# SleepTrackerPoC.net
KiCad netlist of a schematic drawn in Altium Designer
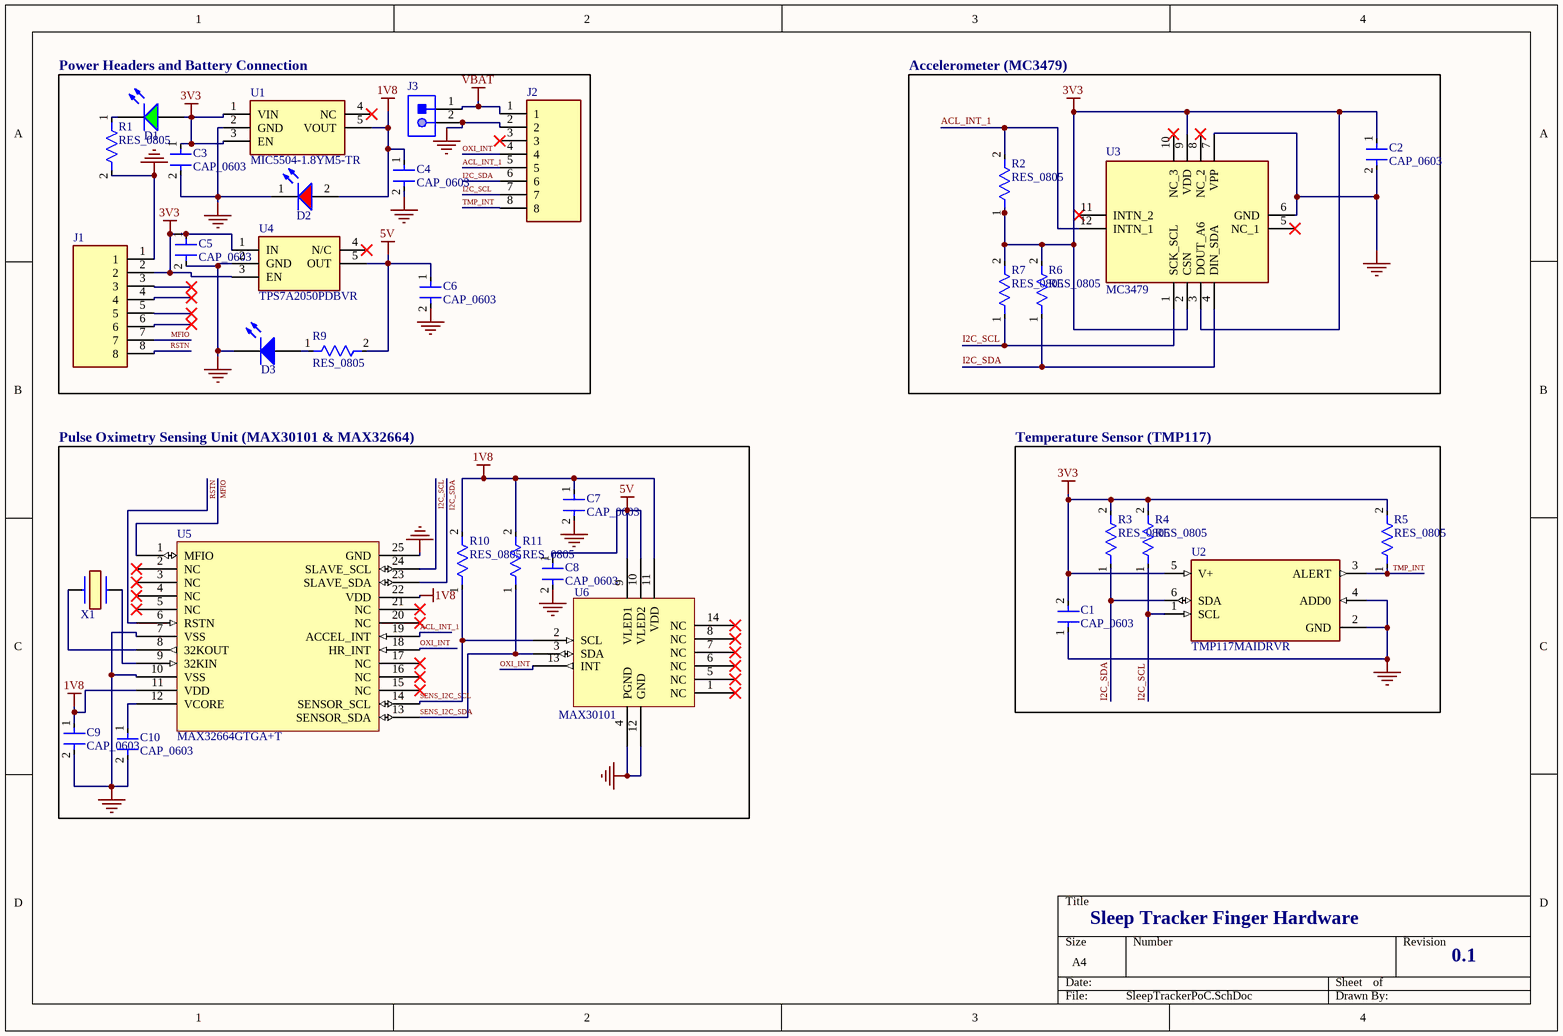
[diagram p0: SleepTrackerPoC.SchDoc]

(export (version "E")
  (design (tool "Eeschema 10.0.6"))
  (components
    (comp (ref "C1")
      (value "CAP_0603")
      (footprint "CAP_0603")
      (libsource (lib "SleepTrackerPoCSchLib") (part "Capacitor SMT 0603"))
    )
    (comp (ref "C2")
      (value "CAP_0603")
      (footprint "CAP_0603")
      (libsource (lib "SleepTrackerPoCSchLib") (part "Capacitor SMT 0603"))
    )
    (comp (ref "C3")
      (value "CAP_0603")
      (footprint "CAP_0603")
      (libsource (lib "SleepTrackerPoCSchLib") (part "Capacitor SMT 0603"))
    )
    (comp (ref "C4")
      (value "CAP_0603")
      (footprint "CAP_0603")
      (libsource (lib "SleepTrackerPoCSchLib") (part "Capacitor SMT 0603"))
    )
    (comp (ref "C5")
      (value "CAP_0603")
      (footprint "CAP_0603")
      (libsource (lib "SleepTrackerPoCSchLib") (part "Capacitor SMT 0603"))
    )
    (comp (ref "C6")
      (value "CAP_0603")
      (footprint "CAP_0603")
      (libsource (lib "SleepTrackerPoCSchLib") (part "Capacitor SMT 0603"))
    )
    (comp (ref "C7")
      (value "CAP_0603")
      (footprint "CAP_0603")
      (libsource (lib "SleepTrackerPoCSchLib") (part "Capacitor SMT 0603"))
    )
    (comp (ref "C8")
      (value "CAP_0603")
      (footprint "CAP_0603")
      (libsource (lib "SleepTrackerPoCSchLib") (part "Capacitor SMT 0603"))
    )
    (comp (ref "C9")
      (value "CAP_0603")
      (footprint "CAP_0603")
      (libsource (lib "SleepTrackerPoCSchLib") (part "Capacitor SMT 0603"))
    )
    (comp (ref "C10")
      (value "CAP_0603")
      (footprint "CAP_0603")
      (libsource (lib "SleepTrackerPoCSchLib") (part "Capacitor SMT 0603"))
    )
    (comp (ref "D1")
      (value "150080VS75000")
      (footprint "WL-SMCW_0805_150080xx75000")
      (description "WL-SMCW SMT Mono-Color Chip LED Waterclear")
      (libsource (lib "Altium Content Vault") (part "LED_Green_2A-1K"))
    )
    (comp (ref "D2")
      (value "150080RS75000")
      (footprint "WL-SMCW_0805_150080xx75000")
      (description "LED Uni-Color Red 630nm 2-Pin Chip 0805(2012Metric) T/R")
      (libsource (lib "Altium Content Vault") (part "LED_Red_2A-1K"))
    )
    (comp (ref "D3")
      (value "150080BS75000")
      (footprint "WL-SMCW_0805_150080xx75000")
      (description "Led, Blue, 470 Nm, 3.2 V, 30 Ma, 145 Mcd Rohs Compliant: Yes")
      (libsource (lib "Altium Content Vault") (part "LED_Blue_2A-1K"))
    )
    (comp (ref "J1")
      (value "90147-1108")
      (footprint "RHDR8W70P0X254_1X8_2017X244X870P")
      (description "Headers & Wire Housings 8CKT VERT SR CON")
      (fields (field (name "MOUSER PART NUMBER") "538-90147-1108"))
      (libsource (lib "SleepTrackerPoCSchLib") (part "90147-1108"))
    )
    (comp (ref "J2")
      (value "90147-1108")
      (footprint "RHDR8W70P0X254_1X8_2017X244X870P")
      (description "Headers & Wire Housings 8CKT VERT SR CON")
      (fields (field (name "MOUSER PART NUMBER") "538-90147-1108"))
      (libsource (lib "") (part "90147-1108_1"))
    )
    (comp (ref "J3")
      (value "S2B-PH-K-S(LF)(SN)")
      (footprint "JST-S2B-PH-K-S_V")
      (fields (field (name "TOLERANCE") "20%"))
      (libsource (lib "Altium Content Vault") (part "CN-1P-M-R2"))
    )
    (comp (ref "R1")
      (value "RES_0805")
      (footprint "RES_0805")
      (libsource (lib "SleepTrackerPoCSchLib") (part "Resistor SMT 0805"))
    )
    (comp (ref "R2")
      (value "RES_0805")
      (footprint "RES_0805")
      (libsource (lib "SleepTrackerPoCSchLib") (part "Resistor SMT 0805"))
    )
    (comp (ref "R3")
      (value "RES_0805")
      (footprint "RES_0805")
      (libsource (lib "SleepTrackerPoCSchLib") (part "Resistor SMT 0805"))
    )
    (comp (ref "R4")
      (value "RES_0805")
      (footprint "RES_0805")
      (libsource (lib "SleepTrackerPoCSchLib") (part "Resistor SMT 0805"))
    )
    (comp (ref "R5")
      (value "RES_0805")
      (footprint "RES_0805")
      (libsource (lib "SleepTrackerPoCSchLib") (part "Resistor SMT 0805"))
    )
    (comp (ref "R6")
      (value "RES_0805")
      (footprint "RES_0805")
      (libsource (lib "SleepTrackerPoCSchLib") (part "Resistor SMT 0805"))
    )
    (comp (ref "R7")
      (value "RES_0805")
      (footprint "RES_0805")
      (libsource (lib "SleepTrackerPoCSchLib") (part "Resistor SMT 0805"))
    )
    (comp (ref "R9")
      (value "RES_0805")
      (footprint "RES_0805")
      (libsource (lib "SleepTrackerPoCSchLib") (part "Resistor SMT 0805"))
    )
    (comp (ref "R10")
      (value "RES_0805")
      (footprint "RES_0805")
      (libsource (lib "SleepTrackerPoCSchLib") (part "Resistor SMT 0805"))
    )
    (comp (ref "R11")
      (value "RES_0805")
      (footprint "RES_0805")
      (libsource (lib "SleepTrackerPoCSchLib") (part "Resistor SMT 0805"))
    )
    (comp (ref "U1")
      (value "MIC5504-1.8YM5-TR")
      (footprint "SOT95P280X145-5N")
      (description "Linear Voltage Regulator IC Positive Fixed Output 1.8V 300mA SOT-23-5")
      (fields (field (name "MOUSER PART NUMBER") "998-MIC5504-1.8YM5TR"))
      (libsource (lib "SleepTrackerPoCSchLib") (part "MIC5504-1.8YM5-TR"))
    )
    (comp (ref "U2")
      (value "TMP117MAIDRVR")
      (footprint "FP-DRV0006B-IPC_C")
      (description "TEMPERATURE SENSOR")
      (libsource (lib "Altium Content Vault") (part "6af1b5b9c3f1ef8afed83eb3745dfc1"))
    )
    (comp (ref "U3")
      (value "MC3479")
      (footprint "MC3479")
      (description "Accelerometers Small Digital 3-axis Accelerometer Sensor")
      (fields (field (name "MOUSER PART NUMBER") "498-MC3479"))
      (libsource (lib "SleepTrackerPoCSchLib") (part "MC3479"))
    )
    (comp (ref "U4")
      (value "TPS7A2050PDBVR")
      (footprint "SOT95P280X145-5N")
      (fields (field (name "MOUSER PART NUMBER") "595-TPS7A2050PDBVR"))
      (libsource (lib "SleepTrackerPoCSchLib") (part "TPS7A2050PDBVR"))
    )
    (comp (ref "U5")
      (value "MAX32664GTGA+T")
      (footprint "MAX32664")
      (description "Maxim Integrated MAX32664GTGA+T Sensor Hub")
      (libsource (lib "SleepTrackerPoCSchLib") (part "MAX32664GTGA+T"))
    )
    (comp (ref "U6")
      (value "MAX30101")
      (footprint "MAX30101")
      (description "Maxim Integrated MAX30101 Oximetry Sensor")
      (libsource (lib "SleepTrackerPoCSchLib") (part "MAX30101"))
    )
    (comp (ref "X1")
      (value "CFS-20632768DZBB")
      (footprint "CFS20632768DZBB")
      (description "32.768 kHz +/-20ppm Crystal 6pF 35 kOhms Cylindrical Can, Radial")
      (fields (field (name "MOUSER PART NUMBER") "695-CFS-20632768DZBB"))
      (libsource (lib "SleepTrackerPoCSchLib") (part "CFS-20632768DZBB"))
    )
  )
  (nets
    (net (code "1") (name "/ACL_INT_1") (class "Default")
      (node (ref "J2") (pin "5") (pinfunction "5_5") (pintype "passive"))
      (node (ref "R2") (pin "2") (pintype "passive"))
      (node (ref "U3") (pin "12") (pinfunction "INTN_1_12") (pintype "passive"))
      (node (ref "U5") (pin "19") (pinfunction "ACCEL_INT_19") (pintype "input"))
    )
    (net (code "2") (name "/I2C_SCL") (class "Default")
      (node (ref "J2") (pin "7") (pinfunction "7_7") (pintype "passive"))
      (node (ref "R4") (pin "1") (pintype "passive"))
      (node (ref "R7") (pin "1") (pintype "passive"))
      (node (ref "U2") (pin "1") (pinfunction "SCL_1") (pintype "input"))
      (node (ref "U3") (pin "1") (pinfunction "SCK_SCL_1") (pintype "passive"))
      (node (ref "U5") (pin "24") (pinfunction "SLAVE_SCL_24") (pintype "bidirectional"))
    )
    (net (code "3") (name "/I2C_SDA") (class "Default")
      (node (ref "J2") (pin "6") (pinfunction "6_6") (pintype "passive"))
      (node (ref "R3") (pin "1") (pintype "passive"))
      (node (ref "R6") (pin "1") (pintype "passive"))
      (node (ref "U2") (pin "6") (pinfunction "SDA_6") (pintype "bidirectional"))
      (node (ref "U3") (pin "4") (pinfunction "DIN_SDA_4") (pintype "passive"))
      (node (ref "U5") (pin "23") (pinfunction "SLAVE_SDA_23") (pintype "bidirectional"))
    )
    (net (code "4") (name "/MFIO") (class "Default")
      (node (ref "J1") (pin "7") (pinfunction "7_7") (pintype "passive"))
      (node (ref "U5") (pin "1") (pinfunction "MFIO_1") (pintype "bidirectional"))
    )
    (net (code "5") (name "/OXI_INT") (class "Default")
      (node (ref "J2") (pin "4") (pinfunction "4_4") (pintype "passive"))
      (node (ref "U5") (pin "18") (pinfunction "HR_INT_18") (pintype "input"))
      (node (ref "U6") (pin "13") (pinfunction "INT_13") (pintype "output"))
    )
    (net (code "6") (name "/RSTN") (class "Default")
      (node (ref "J1") (pin "8") (pinfunction "8_8") (pintype "passive"))
      (node (ref "U5") (pin "6") (pinfunction "RSTN_6") (pintype "input"))
    )
    (net (code "7") (name "/SENS_I2C_SCL") (class "Default")
      (node (ref "R10") (pin "1") (pintype "passive"))
      (node (ref "U5") (pin "14") (pinfunction "SENSOR_SCL_14") (pintype "bidirectional"))
      (node (ref "U6") (pin "2") (pinfunction "SCL_2") (pintype "input"))
    )
    (net (code "8") (name "/SENS_I2C_SDA") (class "Default")
      (node (ref "R11") (pin "1") (pintype "passive"))
      (node (ref "U5") (pin "13") (pinfunction "SENSOR_SDA_13") (pintype "bidirectional"))
      (node (ref "U6") (pin "3") (pinfunction "SDA_3") (pintype "bidirectional"))
    )
    (net (code "9") (name "/TMP_INT") (class "Default")
      (node (ref "J2") (pin "8") (pinfunction "8_8") (pintype "passive"))
      (node (ref "R5") (pin "1") (pintype "passive"))
      (node (ref "U2") (pin "3") (pinfunction "ALERT_3") (pintype "output"))
    )
    (net (code "10") (name "1V8") (class "Default")
      (node (ref "C4") (pin "1") (pintype "passive"))
      (node (ref "C7") (pin "1") (pintype "passive"))
      (node (ref "C9") (pin "1") (pintype "passive"))
      (node (ref "D2") (pin "2") (pinfunction "A_2") (pintype "passive"))
      (node (ref "R10") (pin "2") (pintype "passive"))
      (node (ref "R11") (pin "2") (pintype "passive"))
      (node (ref "U1") (pin "5") (pinfunction "VOUT_5") (pintype "passive"))
      (node (ref "U5") (pin "11") (pinfunction "VDD_11") (pintype "power_in"))
      (node (ref "U5") (pin "22") (pinfunction "VDD_22") (pintype "power_in"))
      (node (ref "U6") (pin "11") (pinfunction "VDD_11") (pintype "power_in"))
    )
    (net (code "11") (name "3V3") (class "Default")
      (node (ref "C1") (pin "2") (pintype "passive"))
      (node (ref "C2") (pin "1") (pintype "passive"))
      (node (ref "C3") (pin "1") (pintype "passive"))
      (node (ref "C5") (pin "1") (pintype "passive"))
      (node (ref "D1") (pin "2") (pinfunction "A_2") (pintype "passive"))
      (node (ref "J1") (pin "2") (pinfunction "2_2") (pintype "passive"))
      (node (ref "R2") (pin "1") (pintype "passive"))
      (node (ref "R3") (pin "2") (pintype "passive"))
      (node (ref "R4") (pin "2") (pintype "passive"))
      (node (ref "R5") (pin "2") (pintype "passive"))
      (node (ref "R6") (pin "2") (pintype "passive"))
      (node (ref "R7") (pin "2") (pintype "passive"))
      (node (ref "U1") (pin "1") (pinfunction "VIN_1") (pintype "passive"))
      (node (ref "U1") (pin "3") (pinfunction "EN_3") (pintype "passive"))
      (node (ref "U2") (pin "5") (pinfunction "V+_5") (pintype "input"))
      (node (ref "U3") (pin "2") (pinfunction "CSN_2") (pintype "passive"))
      (node (ref "U3") (pin "3") (pinfunction "DOUT_A6_3") (pintype "passive"))
      (node (ref "U3") (pin "9") (pinfunction "VDD_9") (pintype "passive"))
      (node (ref "U4") (pin "1") (pinfunction "IN_1") (pintype "passive"))
      (node (ref "U4") (pin "3") (pinfunction "EN_3") (pintype "passive"))
    )
    (net (code "12") (name "5V") (class "Default")
      (node (ref "C6") (pin "1") (pintype "passive"))
      (node (ref "C8") (pin "1") (pintype "passive"))
      (node (ref "R9") (pin "2") (pintype "passive"))
      (node (ref "U4") (pin "5") (pinfunction "OUT_5") (pintype "passive"))
      (node (ref "U6") (pin "10") (pinfunction "VLED2_10") (pintype "power_in"))
      (node (ref "U6") (pin "9") (pinfunction "VLED1_9") (pintype "power_in"))
    )
    (net (code "13") (name "GND") (class "Default")
      (node (ref "C1") (pin "1") (pintype "passive"))
      (node (ref "C10") (pin "2") (pintype "passive"))
      (node (ref "C2") (pin "2") (pintype "passive"))
      (node (ref "C3") (pin "2") (pintype "passive"))
      (node (ref "C4") (pin "2") (pintype "passive"))
      (node (ref "C5") (pin "2") (pintype "passive"))
      (node (ref "C6") (pin "2") (pintype "passive"))
      (node (ref "C7") (pin "2") (pintype "passive"))
      (node (ref "C8") (pin "2") (pintype "passive"))
      (node (ref "C9") (pin "2") (pintype "passive"))
      (node (ref "D2") (pin "1") (pinfunction "K_1") (pintype "passive"))
      (node (ref "D3") (pin "1") (pinfunction "K_1") (pintype "passive"))
      (node (ref "J1") (pin "1") (pinfunction "1_1") (pintype "passive"))
      (node (ref "J2") (pin "2") (pinfunction "2_2") (pintype "passive"))
      (node (ref "J3") (pin "2") (pinfunction "2_2") (pintype "passive"))
      (node (ref "R1") (pin "2") (pintype "passive"))
      (node (ref "U1") (pin "2") (pinfunction "GND_2") (pintype "passive"))
      (node (ref "U2") (pin "2") (pinfunction "GND_2") (pintype "power_in"))
      (node (ref "U2") (pin "4") (pinfunction "ADD0_4") (pintype "input"))
      (node (ref "U3") (pin "6") (pinfunction "GND_6") (pintype "passive"))
      (node (ref "U3") (pin "7") (pinfunction "VPP_7") (pintype "passive"))
      (node (ref "U4") (pin "2") (pinfunction "GND_2") (pintype "passive"))
      (node (ref "U5") (pin "10") (pinfunction "VSS_10") (pintype "power_in"))
      (node (ref "U5") (pin "25") (pinfunction "GND_25") (pintype "power_in"))
      (node (ref "U5") (pin "7") (pinfunction "VSS_7") (pintype "power_in"))
      (node (ref "U6") (pin "12") (pinfunction "GND_12") (pintype "power_in"))
      (node (ref "U6") (pin "4") (pinfunction "PGND_4") (pintype "power_in"))
    )
    (net (code "14") (name "Net-(D1-K)") (class "Default")
      (node (ref "D1") (pin "1") (pinfunction "K_1") (pintype "passive"))
      (node (ref "R1") (pin "1") (pintype "passive"))
    )
    (net (code "15") (name "Net-(D3-A)") (class "Default")
      (node (ref "D3") (pin "2") (pinfunction "A_2") (pintype "passive"))
      (node (ref "R9") (pin "1") (pintype "passive"))
    )
    (net (code "16") (name "Net-(U5-32KIN)") (class "Default")
      (node (ref "U5") (pin "9") (pinfunction "32KIN_9") (pintype "input"))
      (node (ref "X1") (pin "1") (pinfunction "1_1") (pintype "passive"))
    )
    (net (code "17") (name "Net-(U5-32KOUT)") (class "Default")
      (node (ref "U5") (pin "8") (pinfunction "32KOUT_8") (pintype "output"))
      (node (ref "X1") (pin "2") (pinfunction "2_2") (pintype "passive"))
    )
    (net (code "18") (name "Net-(U5-VCORE)") (class "Default")
      (node (ref "C10") (pin "1") (pintype "passive"))
      (node (ref "U5") (pin "12") (pinfunction "VCORE_12") (pintype "power_in"))
    )
    (net (code "19") (name "VBAT") (class "Default")
      (node (ref "J2") (pin "1") (pinfunction "1_1") (pintype "passive"))
      (node (ref "J3") (pin "1") (pinfunction "1_1") (pintype "passive"))
    )
    (net (code "20") (name "unconnected-(J1-Pad3)") (class "Default")
      (node (ref "J1") (pin "3") (pinfunction "3_3") (pintype "passive+no_connect"))
    )
    (net (code "21") (name "unconnected-(J1-Pad4)") (class "Default")
      (node (ref "J1") (pin "4") (pinfunction "4_4") (pintype "passive+no_connect"))
    )
    (net (code "22") (name "unconnected-(J1-Pad5)") (class "Default")
      (node (ref "J1") (pin "5") (pinfunction "5_5") (pintype "passive+no_connect"))
    )
    (net (code "23") (name "unconnected-(J1-Pad6)") (class "Default")
      (node (ref "J1") (pin "6") (pinfunction "6_6") (pintype "passive+no_connect"))
    )
    (net (code "24") (name "unconnected-(J2-Pad3)") (class "Default")
      (node (ref "J2") (pin "3") (pinfunction "3_3") (pintype "passive+no_connect"))
    )
    (net (code "25") (name "unconnected-(U1-NC-Pad4)") (class "Default")
      (node (ref "U1") (pin "4") (pinfunction "NC_4") (pintype "passive+no_connect"))
    )
    (net (code "26") (name "unconnected-(U3-INTN_2-Pad11)") (class "Default")
      (node (ref "U3") (pin "11") (pinfunction "INTN_2_11") (pintype "passive+no_connect"))
    )
    (net (code "27") (name "unconnected-(U3-NC_1-Pad5)") (class "Default")
      (node (ref "U3") (pin "5") (pinfunction "NC_1_5") (pintype "passive+no_connect"))
    )
    (net (code "28") (name "unconnected-(U3-NC_2-Pad8)") (class "Default")
      (node (ref "U3") (pin "8") (pinfunction "NC_2_8") (pintype "passive+no_connect"))
    )
    (net (code "29") (name "unconnected-(U3-NC_3-Pad10)") (class "Default")
      (node (ref "U3") (pin "10") (pinfunction "NC_3_10") (pintype "passive+no_connect"))
    )
    (net (code "30") (name "unconnected-(U4-N{slash}C-Pad4)") (class "Default")
      (node (ref "U4") (pin "4") (pinfunction "N/C_4") (pintype "passive+no_connect"))
    )
    (net (code "31") (name "unconnected-(U5-NC-Pad2)") (class "Default")
      (node (ref "U5") (pin "2") (pinfunction "NC_2") (pintype "passive+no_connect"))
    )
    (net (code "32") (name "unconnected-(U5-NC-Pad3)") (class "Default")
      (node (ref "U5") (pin "3") (pinfunction "NC_3") (pintype "passive+no_connect"))
    )
    (net (code "33") (name "unconnected-(U5-NC-Pad4)") (class "Default")
      (node (ref "U5") (pin "4") (pinfunction "NC_4") (pintype "passive+no_connect"))
    )
    (net (code "34") (name "unconnected-(U5-NC-Pad5)") (class "Default")
      (node (ref "U5") (pin "5") (pinfunction "NC_5") (pintype "passive+no_connect"))
    )
    (net (code "35") (name "unconnected-(U5-NC-Pad15)") (class "Default")
      (node (ref "U5") (pin "15") (pinfunction "NC_15") (pintype "passive+no_connect"))
    )
    (net (code "36") (name "unconnected-(U5-NC-Pad16)") (class "Default")
      (node (ref "U5") (pin "16") (pinfunction "NC_16") (pintype "passive+no_connect"))
    )
    (net (code "37") (name "unconnected-(U5-NC-Pad17)") (class "Default")
      (node (ref "U5") (pin "17") (pinfunction "NC_17") (pintype "passive+no_connect"))
    )
    (net (code "38") (name "unconnected-(U5-NC-Pad20)") (class "Default")
      (node (ref "U5") (pin "20") (pinfunction "NC_20") (pintype "passive+no_connect"))
    )
    (net (code "39") (name "unconnected-(U5-NC-Pad21)") (class "Default")
      (node (ref "U5") (pin "21") (pinfunction "NC_21") (pintype "passive+no_connect"))
    )
    (net (code "40") (name "unconnected-(U6-NC-Pad1)") (class "Default")
      (node (ref "U6") (pin "1") (pinfunction "NC_1") (pintype "passive+no_connect"))
    )
    (net (code "41") (name "unconnected-(U6-NC-Pad5)") (class "Default")
      (node (ref "U6") (pin "5") (pinfunction "NC_5") (pintype "passive+no_connect"))
    )
    (net (code "42") (name "unconnected-(U6-NC-Pad6)") (class "Default")
      (node (ref "U6") (pin "6") (pinfunction "NC_6") (pintype "passive+no_connect"))
    )
    (net (code "43") (name "unconnected-(U6-NC-Pad7)") (class "Default")
      (node (ref "U6") (pin "7") (pinfunction "NC_7") (pintype "passive+no_connect"))
    )
    (net (code "44") (name "unconnected-(U6-NC-Pad8)") (class "Default")
      (node (ref "U6") (pin "8") (pinfunction "NC_8") (pintype "passive+no_connect"))
    )
    (net (code "45") (name "unconnected-(U6-NC-Pad14)") (class "Default")
      (node (ref "U6") (pin "14") (pinfunction "NC_14") (pintype "passive+no_connect"))
    )
  )
)
